# hirose_omnetics_adapter_schematic_rev5.net
KiCad netlist of a schematic drawn in EAGLE
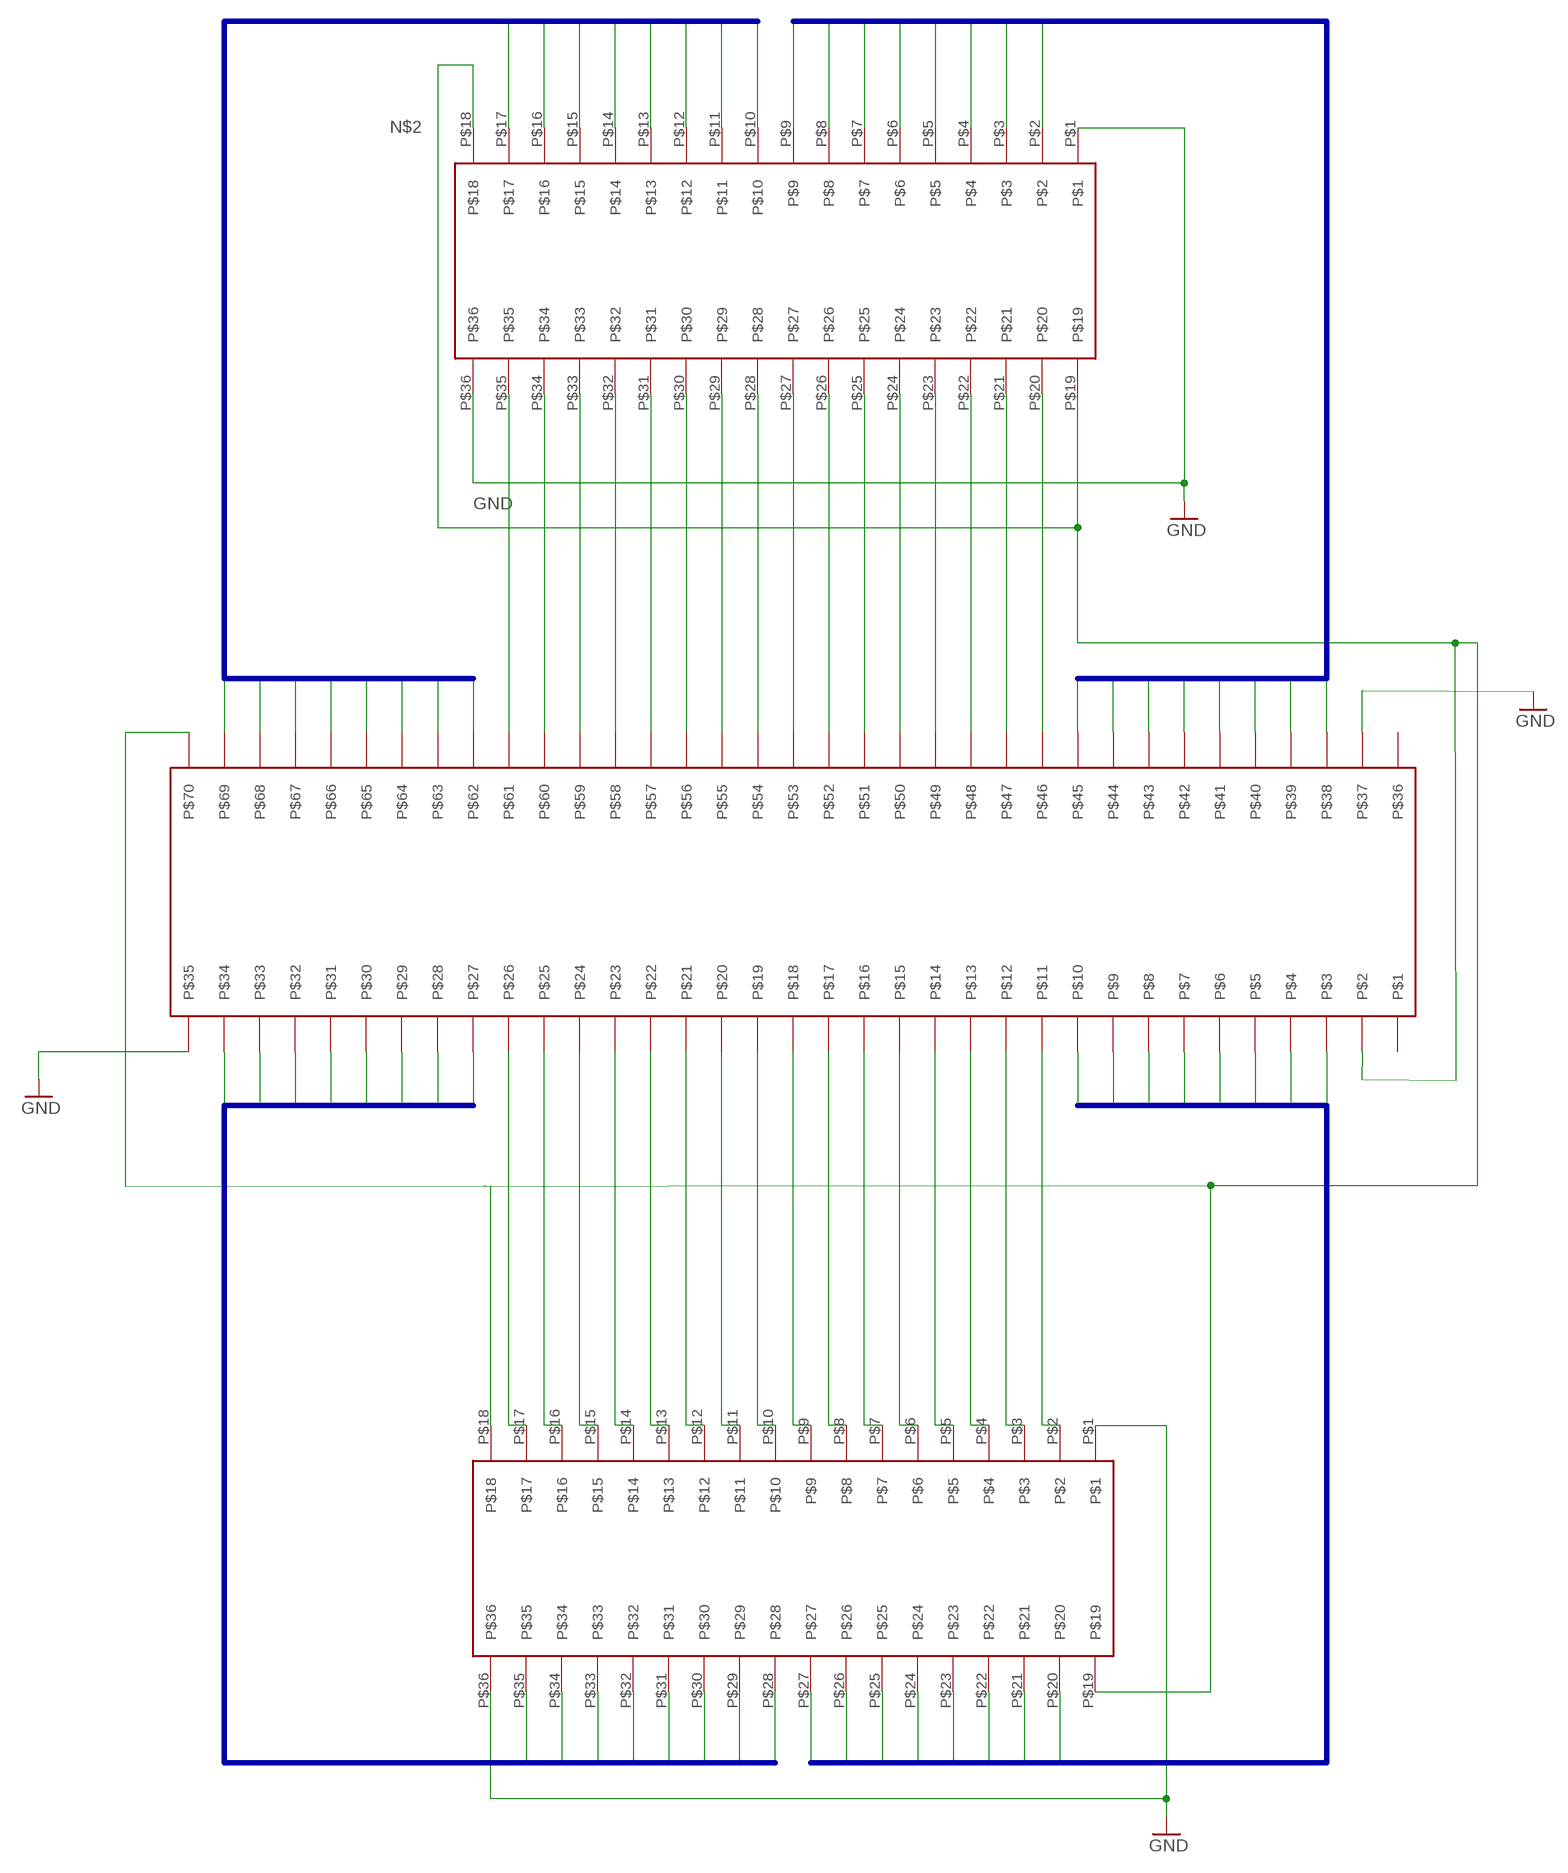
[diagram p0: schematic, sheet 1]

(export (version "E")
  (design (tool "Eeschema 10.0.6"))
  (components
    (comp (ref "U$1")
      (value "HIROSE_DF40_70PIN")
      (footprint "eagle-import:HIROSE_DF40C-70DS")
      (libsource (lib "eagle-import") (part "HIROSE_DF40_70PIN"))
    )
    (comp (ref "U$2")
      (value "OMNETICS_A79026")
      (footprint "eagle-import:OMNETICS_A79026-001")
      (libsource (lib "eagle-import") (part "OMNETICS_A79026"))
    )
    (comp (ref "U$3")
      (value "OMNETICS_A79026")
      (footprint "eagle-import:OMNETICS_A79026-001")
      (libsource (lib "eagle-import") (part "OMNETICS_A79026"))
    )
  )
  (nets
    (net (code "1") (name "/A0") (class "Default")
      (node (ref "U$1") (pin "P$69") (pinfunction "P$69_P$69") (pintype "bidirectional"))
      (node (ref "U$2") (pin "P$10") (pinfunction "P$10_P$10") (pintype "bidirectional"))
    )
    (net (code "2") (name "/A1") (class "Default")
      (node (ref "U$1") (pin "P$68") (pinfunction "P$68_P$68") (pintype "bidirectional"))
      (node (ref "U$2") (pin "P$11") (pinfunction "P$11_P$11") (pintype "bidirectional"))
    )
    (net (code "3") (name "/A2") (class "Default")
      (node (ref "U$1") (pin "P$67") (pinfunction "P$67_P$67") (pintype "bidirectional"))
      (node (ref "U$2") (pin "P$12") (pinfunction "P$12_P$12") (pintype "bidirectional"))
    )
    (net (code "4") (name "/A3") (class "Default")
      (node (ref "U$1") (pin "P$66") (pinfunction "P$66_P$66") (pintype "bidirectional"))
      (node (ref "U$2") (pin "P$13") (pinfunction "P$13_P$13") (pintype "bidirectional"))
    )
    (net (code "5") (name "/A4") (class "Default")
      (node (ref "U$1") (pin "P$65") (pinfunction "P$65_P$65") (pintype "bidirectional"))
      (node (ref "U$2") (pin "P$14") (pinfunction "P$14_P$14") (pintype "bidirectional"))
    )
    (net (code "6") (name "/A5") (class "Default")
      (node (ref "U$1") (pin "P$64") (pinfunction "P$64_P$64") (pintype "bidirectional"))
      (node (ref "U$2") (pin "P$15") (pinfunction "P$15_P$15") (pintype "bidirectional"))
    )
    (net (code "7") (name "/A6") (class "Default")
      (node (ref "U$1") (pin "P$63") (pinfunction "P$63_P$63") (pintype "bidirectional"))
      (node (ref "U$2") (pin "P$16") (pinfunction "P$16_P$16") (pintype "bidirectional"))
    )
    (net (code "8") (name "/A7") (class "Default")
      (node (ref "U$1") (pin "P$62") (pinfunction "P$62_P$62") (pintype "bidirectional"))
      (node (ref "U$2") (pin "P$17") (pinfunction "P$17_P$17") (pintype "bidirectional"))
    )
    (net (code "9") (name "/B0") (class "Default")
      (node (ref "U$1") (pin "P$38") (pinfunction "P$38_P$38") (pintype "bidirectional"))
      (node (ref "U$2") (pin "P$9") (pinfunction "P$9_P$9") (pintype "bidirectional"))
    )
    (net (code "10") (name "/B1") (class "Default")
      (node (ref "U$1") (pin "P$39") (pinfunction "P$39_P$39") (pintype "bidirectional"))
      (node (ref "U$2") (pin "P$8") (pinfunction "P$8_P$8") (pintype "bidirectional"))
    )
    (net (code "11") (name "/B2") (class "Default")
      (node (ref "U$1") (pin "P$40") (pinfunction "P$40_P$40") (pintype "bidirectional"))
      (node (ref "U$2") (pin "P$7") (pinfunction "P$7_P$7") (pintype "bidirectional"))
    )
    (net (code "12") (name "/B3") (class "Default")
      (node (ref "U$1") (pin "P$41") (pinfunction "P$41_P$41") (pintype "bidirectional"))
      (node (ref "U$2") (pin "P$6") (pinfunction "P$6_P$6") (pintype "bidirectional"))
    )
    (net (code "13") (name "/B4") (class "Default")
      (node (ref "U$1") (pin "P$42") (pinfunction "P$42_P$42") (pintype "bidirectional"))
      (node (ref "U$2") (pin "P$5") (pinfunction "P$5_P$5") (pintype "bidirectional"))
    )
    (net (code "14") (name "/B5") (class "Default")
      (node (ref "U$1") (pin "P$43") (pinfunction "P$43_P$43") (pintype "bidirectional"))
      (node (ref "U$2") (pin "P$4") (pinfunction "P$4_P$4") (pintype "bidirectional"))
    )
    (net (code "15") (name "/B6") (class "Default")
      (node (ref "U$1") (pin "P$44") (pinfunction "P$44_P$44") (pintype "bidirectional"))
      (node (ref "U$2") (pin "P$3") (pinfunction "P$3_P$3") (pintype "bidirectional"))
    )
    (net (code "16") (name "/B7") (class "Default")
      (node (ref "U$1") (pin "P$45") (pinfunction "P$45_P$45") (pintype "bidirectional"))
      (node (ref "U$2") (pin "P$2") (pinfunction "P$2_P$2") (pintype "bidirectional"))
    )
    (net (code "17") (name "/C0") (class "Default")
      (node (ref "U$1") (pin "P$34") (pinfunction "P$34_P$34") (pintype "bidirectional"))
      (node (ref "U$3") (pin "P$28") (pinfunction "P$28_P$28") (pintype "bidirectional"))
    )
    (net (code "18") (name "/C1") (class "Default")
      (node (ref "U$1") (pin "P$33") (pinfunction "P$33_P$33") (pintype "bidirectional"))
      (node (ref "U$3") (pin "P$29") (pinfunction "P$29_P$29") (pintype "bidirectional"))
    )
    (net (code "19") (name "/C2") (class "Default")
      (node (ref "U$1") (pin "P$32") (pinfunction "P$32_P$32") (pintype "bidirectional"))
      (node (ref "U$3") (pin "P$30") (pinfunction "P$30_P$30") (pintype "bidirectional"))
    )
    (net (code "20") (name "/C3") (class "Default")
      (node (ref "U$1") (pin "P$31") (pinfunction "P$31_P$31") (pintype "bidirectional"))
      (node (ref "U$3") (pin "P$31") (pinfunction "P$31_P$31") (pintype "bidirectional"))
    )
    (net (code "21") (name "/C4") (class "Default")
      (node (ref "U$1") (pin "P$30") (pinfunction "P$30_P$30") (pintype "bidirectional"))
      (node (ref "U$3") (pin "P$32") (pinfunction "P$32_P$32") (pintype "bidirectional"))
    )
    (net (code "22") (name "/C5") (class "Default")
      (node (ref "U$1") (pin "P$29") (pinfunction "P$29_P$29") (pintype "bidirectional"))
      (node (ref "U$3") (pin "P$33") (pinfunction "P$33_P$33") (pintype "bidirectional"))
    )
    (net (code "23") (name "/C6") (class "Default")
      (node (ref "U$1") (pin "P$28") (pinfunction "P$28_P$28") (pintype "bidirectional"))
      (node (ref "U$3") (pin "P$34") (pinfunction "P$34_P$34") (pintype "bidirectional"))
    )
    (net (code "24") (name "/C7") (class "Default")
      (node (ref "U$1") (pin "P$27") (pinfunction "P$27_P$27") (pintype "bidirectional"))
      (node (ref "U$3") (pin "P$35") (pinfunction "P$35_P$35") (pintype "bidirectional"))
    )
    (net (code "25") (name "/D0") (class "Default")
      (node (ref "U$1") (pin "P$3") (pinfunction "P$3_P$3") (pintype "bidirectional"))
      (node (ref "U$3") (pin "P$27") (pinfunction "P$27_P$27") (pintype "bidirectional"))
    )
    (net (code "26") (name "/D1") (class "Default")
      (node (ref "U$1") (pin "P$4") (pinfunction "P$4_P$4") (pintype "bidirectional"))
      (node (ref "U$3") (pin "P$26") (pinfunction "P$26_P$26") (pintype "bidirectional"))
    )
    (net (code "27") (name "/D2") (class "Default")
      (node (ref "U$1") (pin "P$5") (pinfunction "P$5_P$5") (pintype "bidirectional"))
      (node (ref "U$3") (pin "P$25") (pinfunction "P$25_P$25") (pintype "bidirectional"))
    )
    (net (code "28") (name "/D3") (class "Default")
      (node (ref "U$1") (pin "P$6") (pinfunction "P$6_P$6") (pintype "bidirectional"))
      (node (ref "U$3") (pin "P$24") (pinfunction "P$24_P$24") (pintype "bidirectional"))
    )
    (net (code "29") (name "/D4") (class "Default")
      (node (ref "U$1") (pin "P$7") (pinfunction "P$7_P$7") (pintype "bidirectional"))
      (node (ref "U$3") (pin "P$23") (pinfunction "P$23_P$23") (pintype "bidirectional"))
    )
    (net (code "30") (name "/D5") (class "Default")
      (node (ref "U$1") (pin "P$8") (pinfunction "P$8_P$8") (pintype "bidirectional"))
      (node (ref "U$3") (pin "P$22") (pinfunction "P$22_P$22") (pintype "bidirectional"))
    )
    (net (code "31") (name "/D6") (class "Default")
      (node (ref "U$1") (pin "P$9") (pinfunction "P$9_P$9") (pintype "bidirectional"))
      (node (ref "U$3") (pin "P$21") (pinfunction "P$21_P$21") (pintype "bidirectional"))
    )
    (net (code "32") (name "/D7") (class "Default")
      (node (ref "U$1") (pin "P$10") (pinfunction "P$10_P$10") (pintype "bidirectional"))
      (node (ref "U$3") (pin "P$20") (pinfunction "P$20_P$20") (pintype "bidirectional"))
    )
    (net (code "33") (name "/N$2") (class "Default")
      (node (ref "U$1") (pin "P$2") (pinfunction "P$2_P$2") (pintype "bidirectional"))
      (node (ref "U$1") (pin "P$70") (pinfunction "P$70_P$70") (pintype "bidirectional"))
      (node (ref "U$2") (pin "P$18") (pinfunction "P$18_P$18") (pintype "bidirectional"))
      (node (ref "U$2") (pin "P$19") (pinfunction "P$19_P$19") (pintype "bidirectional"))
      (node (ref "U$3") (pin "P$18") (pinfunction "P$18_P$18") (pintype "bidirectional"))
      (node (ref "U$3") (pin "P$19") (pinfunction "P$19_P$19") (pintype "bidirectional"))
    )
    (net (code "34") (name "GND") (class "Default")
      (node (ref "U$1") (pin "P$35") (pinfunction "P$35_P$35") (pintype "bidirectional"))
      (node (ref "U$1") (pin "P$37") (pinfunction "P$37_P$37") (pintype "bidirectional"))
      (node (ref "U$2") (pin "P$1") (pinfunction "P$1_P$1") (pintype "bidirectional"))
      (node (ref "U$2") (pin "P$36") (pinfunction "P$36_P$36") (pintype "bidirectional"))
      (node (ref "U$3") (pin "P$1") (pinfunction "P$1_P$1") (pintype "bidirectional"))
      (node (ref "U$3") (pin "P$36") (pinfunction "P$36_P$36") (pintype "bidirectional"))
    )
    (net (code "35") (name "Net-(U$1-PadP$11)") (class "Default")
      (node (ref "U$1") (pin "P$11") (pinfunction "P$11_P$11") (pintype "bidirectional"))
      (node (ref "U$3") (pin "P$2") (pinfunction "P$2_P$2") (pintype "bidirectional"))
    )
    (net (code "36") (name "Net-(U$1-PadP$12)") (class "Default")
      (node (ref "U$1") (pin "P$12") (pinfunction "P$12_P$12") (pintype "bidirectional"))
      (node (ref "U$3") (pin "P$3") (pinfunction "P$3_P$3") (pintype "bidirectional"))
    )
    (net (code "37") (name "Net-(U$1-PadP$13)") (class "Default")
      (node (ref "U$1") (pin "P$13") (pinfunction "P$13_P$13") (pintype "bidirectional"))
      (node (ref "U$3") (pin "P$4") (pinfunction "P$4_P$4") (pintype "bidirectional"))
    )
    (net (code "38") (name "Net-(U$1-PadP$14)") (class "Default")
      (node (ref "U$1") (pin "P$14") (pinfunction "P$14_P$14") (pintype "bidirectional"))
      (node (ref "U$3") (pin "P$5") (pinfunction "P$5_P$5") (pintype "bidirectional"))
    )
    (net (code "39") (name "Net-(U$1-PadP$15)") (class "Default")
      (node (ref "U$1") (pin "P$15") (pinfunction "P$15_P$15") (pintype "bidirectional"))
      (node (ref "U$3") (pin "P$6") (pinfunction "P$6_P$6") (pintype "bidirectional"))
    )
    (net (code "40") (name "Net-(U$1-PadP$16)") (class "Default")
      (node (ref "U$1") (pin "P$16") (pinfunction "P$16_P$16") (pintype "bidirectional"))
      (node (ref "U$3") (pin "P$7") (pinfunction "P$7_P$7") (pintype "bidirectional"))
    )
    (net (code "41") (name "Net-(U$1-PadP$17)") (class "Default")
      (node (ref "U$1") (pin "P$17") (pinfunction "P$17_P$17") (pintype "bidirectional"))
      (node (ref "U$3") (pin "P$8") (pinfunction "P$8_P$8") (pintype "bidirectional"))
    )
    (net (code "42") (name "Net-(U$1-PadP$18)") (class "Default")
      (node (ref "U$1") (pin "P$18") (pinfunction "P$18_P$18") (pintype "bidirectional"))
      (node (ref "U$3") (pin "P$9") (pinfunction "P$9_P$9") (pintype "bidirectional"))
    )
    (net (code "43") (name "Net-(U$1-PadP$19)") (class "Default")
      (node (ref "U$1") (pin "P$19") (pinfunction "P$19_P$19") (pintype "bidirectional"))
      (node (ref "U$3") (pin "P$10") (pinfunction "P$10_P$10") (pintype "bidirectional"))
    )
    (net (code "44") (name "Net-(U$1-PadP$20)") (class "Default")
      (node (ref "U$1") (pin "P$20") (pinfunction "P$20_P$20") (pintype "bidirectional"))
      (node (ref "U$3") (pin "P$11") (pinfunction "P$11_P$11") (pintype "bidirectional"))
    )
    (net (code "45") (name "Net-(U$1-PadP$21)") (class "Default")
      (node (ref "U$1") (pin "P$21") (pinfunction "P$21_P$21") (pintype "bidirectional"))
      (node (ref "U$3") (pin "P$12") (pinfunction "P$12_P$12") (pintype "bidirectional"))
    )
    (net (code "46") (name "Net-(U$1-PadP$22)") (class "Default")
      (node (ref "U$1") (pin "P$22") (pinfunction "P$22_P$22") (pintype "bidirectional"))
      (node (ref "U$3") (pin "P$13") (pinfunction "P$13_P$13") (pintype "bidirectional"))
    )
    (net (code "47") (name "Net-(U$1-PadP$23)") (class "Default")
      (node (ref "U$1") (pin "P$23") (pinfunction "P$23_P$23") (pintype "bidirectional"))
      (node (ref "U$3") (pin "P$14") (pinfunction "P$14_P$14") (pintype "bidirectional"))
    )
    (net (code "48") (name "Net-(U$1-PadP$24)") (class "Default")
      (node (ref "U$1") (pin "P$24") (pinfunction "P$24_P$24") (pintype "bidirectional"))
      (node (ref "U$3") (pin "P$15") (pinfunction "P$15_P$15") (pintype "bidirectional"))
    )
    (net (code "49") (name "Net-(U$1-PadP$25)") (class "Default")
      (node (ref "U$1") (pin "P$25") (pinfunction "P$25_P$25") (pintype "bidirectional"))
      (node (ref "U$3") (pin "P$16") (pinfunction "P$16_P$16") (pintype "bidirectional"))
    )
    (net (code "50") (name "Net-(U$1-PadP$26)") (class "Default")
      (node (ref "U$1") (pin "P$26") (pinfunction "P$26_P$26") (pintype "bidirectional"))
      (node (ref "U$3") (pin "P$17") (pinfunction "P$17_P$17") (pintype "bidirectional"))
    )
    (net (code "51") (name "Net-(U$1-PadP$46)") (class "Default")
      (node (ref "U$1") (pin "P$46") (pinfunction "P$46_P$46") (pintype "bidirectional"))
      (node (ref "U$2") (pin "P$20") (pinfunction "P$20_P$20") (pintype "bidirectional"))
    )
    (net (code "52") (name "Net-(U$1-PadP$47)") (class "Default")
      (node (ref "U$1") (pin "P$47") (pinfunction "P$47_P$47") (pintype "bidirectional"))
      (node (ref "U$2") (pin "P$21") (pinfunction "P$21_P$21") (pintype "bidirectional"))
    )
    (net (code "53") (name "Net-(U$1-PadP$48)") (class "Default")
      (node (ref "U$1") (pin "P$48") (pinfunction "P$48_P$48") (pintype "bidirectional"))
      (node (ref "U$2") (pin "P$22") (pinfunction "P$22_P$22") (pintype "bidirectional"))
    )
    (net (code "54") (name "Net-(U$1-PadP$49)") (class "Default")
      (node (ref "U$1") (pin "P$49") (pinfunction "P$49_P$49") (pintype "bidirectional"))
      (node (ref "U$2") (pin "P$23") (pinfunction "P$23_P$23") (pintype "bidirectional"))
    )
    (net (code "55") (name "Net-(U$1-PadP$50)") (class "Default")
      (node (ref "U$1") (pin "P$50") (pinfunction "P$50_P$50") (pintype "bidirectional"))
      (node (ref "U$2") (pin "P$24") (pinfunction "P$24_P$24") (pintype "bidirectional"))
    )
    (net (code "56") (name "Net-(U$1-PadP$51)") (class "Default")
      (node (ref "U$1") (pin "P$51") (pinfunction "P$51_P$51") (pintype "bidirectional"))
      (node (ref "U$2") (pin "P$25") (pinfunction "P$25_P$25") (pintype "bidirectional"))
    )
    (net (code "57") (name "Net-(U$1-PadP$52)") (class "Default")
      (node (ref "U$1") (pin "P$52") (pinfunction "P$52_P$52") (pintype "bidirectional"))
      (node (ref "U$2") (pin "P$26") (pinfunction "P$26_P$26") (pintype "bidirectional"))
    )
    (net (code "58") (name "Net-(U$1-PadP$53)") (class "Default")
      (node (ref "U$1") (pin "P$53") (pinfunction "P$53_P$53") (pintype "bidirectional"))
      (node (ref "U$2") (pin "P$27") (pinfunction "P$27_P$27") (pintype "bidirectional"))
    )
    (net (code "59") (name "Net-(U$1-PadP$54)") (class "Default")
      (node (ref "U$1") (pin "P$54") (pinfunction "P$54_P$54") (pintype "bidirectional"))
      (node (ref "U$2") (pin "P$28") (pinfunction "P$28_P$28") (pintype "bidirectional"))
    )
    (net (code "60") (name "Net-(U$1-PadP$55)") (class "Default")
      (node (ref "U$1") (pin "P$55") (pinfunction "P$55_P$55") (pintype "bidirectional"))
      (node (ref "U$2") (pin "P$29") (pinfunction "P$29_P$29") (pintype "bidirectional"))
    )
    (net (code "61") (name "Net-(U$1-PadP$56)") (class "Default")
      (node (ref "U$1") (pin "P$56") (pinfunction "P$56_P$56") (pintype "bidirectional"))
      (node (ref "U$2") (pin "P$30") (pinfunction "P$30_P$30") (pintype "bidirectional"))
    )
    (net (code "62") (name "Net-(U$1-PadP$57)") (class "Default")
      (node (ref "U$1") (pin "P$57") (pinfunction "P$57_P$57") (pintype "bidirectional"))
      (node (ref "U$2") (pin "P$31") (pinfunction "P$31_P$31") (pintype "bidirectional"))
    )
    (net (code "63") (name "Net-(U$1-PadP$58)") (class "Default")
      (node (ref "U$1") (pin "P$58") (pinfunction "P$58_P$58") (pintype "bidirectional"))
      (node (ref "U$2") (pin "P$32") (pinfunction "P$32_P$32") (pintype "bidirectional"))
    )
    (net (code "64") (name "Net-(U$1-PadP$59)") (class "Default")
      (node (ref "U$1") (pin "P$59") (pinfunction "P$59_P$59") (pintype "bidirectional"))
      (node (ref "U$2") (pin "P$33") (pinfunction "P$33_P$33") (pintype "bidirectional"))
    )
    (net (code "65") (name "Net-(U$1-PadP$60)") (class "Default")
      (node (ref "U$1") (pin "P$60") (pinfunction "P$60_P$60") (pintype "bidirectional"))
      (node (ref "U$2") (pin "P$34") (pinfunction "P$34_P$34") (pintype "bidirectional"))
    )
    (net (code "66") (name "Net-(U$1-PadP$61)") (class "Default")
      (node (ref "U$1") (pin "P$61") (pinfunction "P$61_P$61") (pintype "bidirectional"))
      (node (ref "U$2") (pin "P$35") (pinfunction "P$35_P$35") (pintype "bidirectional"))
    )
    (net (code "67") (name "unconnected-(U$1-PadP$1)") (class "Default")
      (node (ref "U$1") (pin "P$1") (pinfunction "P$1_P$1") (pintype "bidirectional"))
    )
    (net (code "68") (name "unconnected-(U$1-PadP$36)") (class "Default")
      (node (ref "U$1") (pin "P$36") (pinfunction "P$36_P$36") (pintype "bidirectional"))
    )
  )
)
